# ESP32_USB_INTERFACE_NOESP.net
KiCad netlist of a schematic drawn in EAGLE
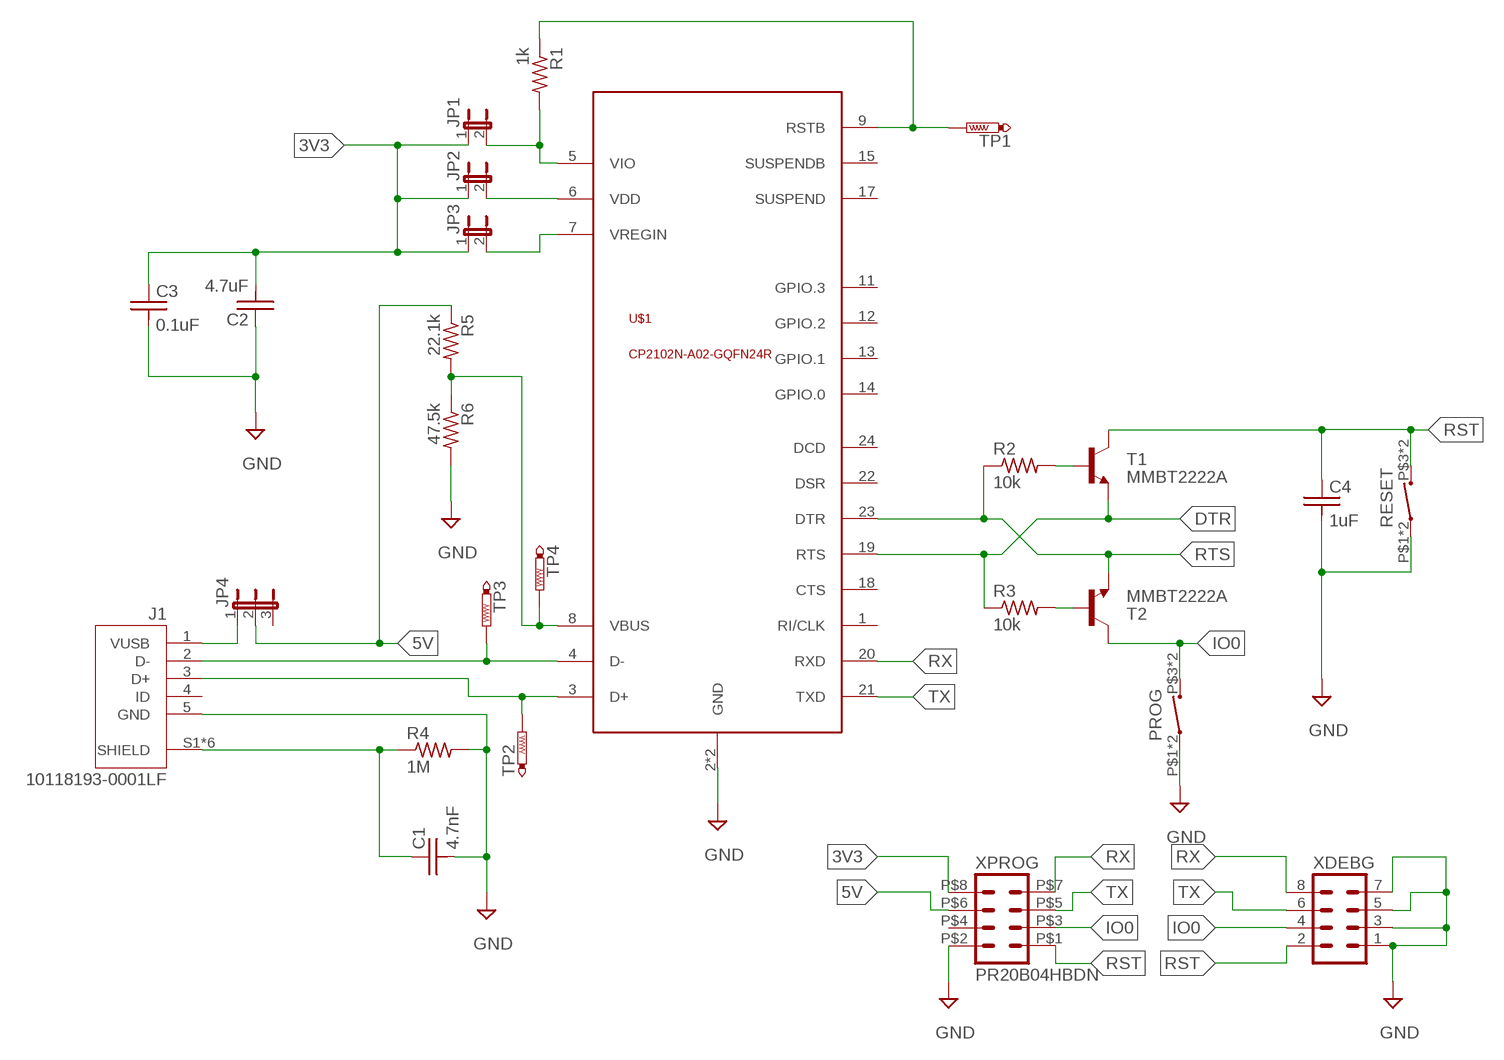
[diagram p0: schematic, sheet 1]

(export (version "E")
  (design (tool "Eeschema 10.0.6"))
  (components
    (comp (ref "C1")
      (value "4.7nF")
      (footprint "eagle-import:C0603")
      (libsource (lib "eagle-import") (part "C0603"))
    )
    (comp (ref "C2")
      (value "4.7uF")
      (footprint "eagle-import:C0603")
      (libsource (lib "eagle-import") (part "C0603"))
    )
    (comp (ref "C3")
      (value "0.1uF")
      (footprint "eagle-import:C0603")
      (libsource (lib "eagle-import") (part "C0603"))
    )
    (comp (ref "C4")
      (value "1uF")
      (footprint "eagle-import:C0603")
      (libsource (lib "eagle-import") (part "C0603"))
    )
    (comp (ref "J1")
      (value "10118193-0001LF")
      (footprint "eagle-import:FCI_10118193-0001LF")
      (fields (field (name "DIGI-KEY_PART_NUMBER") "609-4616-1-ND") (field (name "MF") "Amphenol ICC"))
      (libsource (lib "eagle-import") (part "10118193-0001LF"))
    )
    (comp (ref "JP1")
      (value "JP1E")
      (footprint "eagle-import:JP1")
      (libsource (lib "eagle-import") (part "JP1E"))
    )
    (comp (ref "JP2")
      (value "JP1E")
      (footprint "eagle-import:JP1")
      (libsource (lib "eagle-import") (part "JP1E"))
    )
    (comp (ref "JP3")
      (value "JP1E")
      (footprint "eagle-import:JP1")
      (libsource (lib "eagle-import") (part "JP1E"))
    )
    (comp (ref "JP4")
      (value "JP2E")
      (footprint "eagle-import:JP2")
      (libsource (lib "eagle-import") (part "JP2E"))
    )
    (comp (ref "PROG")
      (value "MOMENTARY_SWITCH")
      (footprint "eagle-import:PTS645")
      (libsource (lib "eagle-import") (part "MOMENTARY_SWITCH"))
    )
    (comp (ref "R1")
      (value "1k")
      (footprint "eagle-import:R0603")
      (libsource (lib "eagle-import") (part "R0603"))
    )
    (comp (ref "R2")
      (value "10k")
      (footprint "eagle-import:R0603")
      (libsource (lib "eagle-import") (part "R0603"))
    )
    (comp (ref "R3")
      (value "10k")
      (footprint "eagle-import:R0603")
      (libsource (lib "eagle-import") (part "R0603"))
    )
    (comp (ref "R4")
      (value "1M")
      (footprint "eagle-import:R0603")
      (libsource (lib "eagle-import") (part "R0603"))
    )
    (comp (ref "R5")
      (value "22.1k")
      (footprint "eagle-import:R0603")
      (libsource (lib "eagle-import") (part "R0603"))
    )
    (comp (ref "R6")
      (value "47.5k")
      (footprint "eagle-import:R0603")
      (libsource (lib "eagle-import") (part "R0603"))
    )
    (comp (ref "RESET")
      (value "MOMENTARY_SWITCH")
      (footprint "eagle-import:PTS645")
      (libsource (lib "eagle-import") (part "MOMENTARY_SWITCH"))
    )
    (comp (ref "T1")
      (value "MMBT2222A")
      (footprint "eagle-import:SOT23-BEC")
      (libsource (lib "eagle-import") (part "-NPN-SOT23-BECMMBT2222ALT1"))
    )
    (comp (ref "T2")
      (value "MMBT2222A")
      (footprint "eagle-import:SOT23-BEC")
      (libsource (lib "eagle-import") (part "-NPN-SOT23-BECMMBT2222ALT1"))
    )
    (comp (ref "TP1")
      (value "PTR1TP10R")
      (footprint "eagle-import:TP10R")
      (libsource (lib "eagle-import") (part "PTR1TP10R"))
    )
    (comp (ref "TP2")
      (value "PTR1TP10R")
      (footprint "eagle-import:TP10R")
      (libsource (lib "eagle-import") (part "PTR1TP10R"))
    )
    (comp (ref "TP3")
      (value "PTR1TP10R")
      (footprint "eagle-import:TP10R")
      (libsource (lib "eagle-import") (part "PTR1TP10R"))
    )
    (comp (ref "TP4")
      (value "PTR1TP10R")
      (footprint "eagle-import:TP10R")
      (libsource (lib "eagle-import") (part "PTR1TP10R"))
    )
    (comp (ref "U$1")
      (value "CP2102N-A02-GQFN24R")
      (footprint "eagle-import:QFN24-4X4")
      (libsource (lib "eagle-import") (part "CP2102N-A02-GQFN24R"))
    )
    (comp (ref "XDEBG")
      (value "MA04-2")
      (footprint "eagle-import:MA04-2")
      (libsource (lib "eagle-import") (part "MA04-2"))
    )
    (comp (ref "XPROG")
      (value "PR20B04HBDN")
      (footprint "eagle-import:PR20B04HBDN")
      (libsource (lib "eagle-import") (part "PR20B04HBDN"))
    )
  )
  (nets
    (net (code "1") (name "3V3") (class "Default")
      (node (ref "C2") (pin "2") (pinfunction "2_2") (pintype "passive"))
      (node (ref "C3") (pin "1") (pinfunction "1_1") (pintype "passive"))
      (node (ref "JP1") (pin "1") (pinfunction "1_1") (pintype "passive"))
      (node (ref "JP2") (pin "1") (pinfunction "1_1") (pintype "passive"))
      (node (ref "JP3") (pin "1") (pinfunction "1_1") (pintype "passive"))
      (node (ref "XPROG") (pin "P$8") (pinfunction "8_P$8") (pintype "passive"))
    )
    (net (code "2") (name "5V") (class "Default")
      (node (ref "JP4") (pin "2") (pinfunction "2_2") (pintype "passive"))
      (node (ref "R5") (pin "1") (pinfunction "1_1") (pintype "passive"))
      (node (ref "XPROG") (pin "P$6") (pinfunction "6_P$6") (pintype "passive"))
    )
    (net (code "3") (name "DTR") (class "Default")
      (node (ref "R3") (pin "1") (pinfunction "1_1") (pintype "passive"))
      (node (ref "T1") (pin "E") (pinfunction "E_E") (pintype "passive"))
      (node (ref "U$1") (pin "19") (pinfunction "RTS_19") (pintype "bidirectional"))
    )
    (net (code "4") (name "GND") (class "Default")
      (node (ref "C1") (pin "2") (pinfunction "2_2") (pintype "passive"))
      (node (ref "C2") (pin "1") (pinfunction "1_1") (pintype "passive"))
      (node (ref "C3") (pin "2") (pinfunction "2_2") (pintype "passive"))
      (node (ref "C4") (pin "2") (pinfunction "2_2") (pintype "passive"))
      (node (ref "J1") (pin "5") (pinfunction "GND_5") (pintype "passive"))
      (node (ref "PROG") (pin "P$1") (pinfunction "1_P$1") (pintype "passive"))
      (node (ref "PROG") (pin "P$2") (pinfunction "1_P$2") (pintype "passive"))
      (node (ref "R4") (pin "2") (pinfunction "2_2") (pintype "passive"))
      (node (ref "R6") (pin "2") (pinfunction "2_2") (pintype "passive"))
      (node (ref "RESET") (pin "P$1") (pinfunction "1_P$1") (pintype "passive"))
      (node (ref "RESET") (pin "P$2") (pinfunction "1_P$2") (pintype "passive"))
      (node (ref "U$1") (pin "2") (pinfunction "GND_2") (pintype "bidirectional"))
      (node (ref "U$1") (pin "EXP") (pinfunction "GND_EXP") (pintype "bidirectional"))
      (node (ref "XDEBG") (pin "1") (pinfunction "1_1") (pintype "passive"))
      (node (ref "XDEBG") (pin "3") (pinfunction "3_3") (pintype "passive"))
      (node (ref "XDEBG") (pin "5") (pinfunction "5_5") (pintype "passive"))
      (node (ref "XDEBG") (pin "7") (pinfunction "7_7") (pintype "passive"))
      (node (ref "XPROG") (pin "P$2") (pinfunction "2_P$2") (pintype "passive"))
    )
    (net (code "5") (name "IO0") (class "Default")
      (node (ref "PROG") (pin "P$3") (pinfunction "2_P$3") (pintype "passive"))
      (node (ref "PROG") (pin "P$4") (pinfunction "2_P$4") (pintype "passive"))
      (node (ref "T2") (pin "C") (pinfunction "C_C") (pintype "passive"))
      (node (ref "XDEBG") (pin "4") (pinfunction "4_4") (pintype "passive"))
      (node (ref "XPROG") (pin "P$3") (pinfunction "3_P$3") (pintype "passive"))
    )
    (net (code "6") (name "Net-(C1-Pad1)") (class "Default")
      (node (ref "C1") (pin "1") (pinfunction "1_1") (pintype "passive"))
      (node (ref "J1") (pin "S1") (pinfunction "SHIELD_S1") (pintype "passive"))
      (node (ref "J1") (pin "S2") (pinfunction "SHIELD_S2") (pintype "passive"))
      (node (ref "J1") (pin "S3") (pinfunction "SHIELD_S3") (pintype "passive"))
      (node (ref "J1") (pin "S4") (pinfunction "SHIELD_S4") (pintype "passive"))
      (node (ref "J1") (pin "S5") (pinfunction "SHIELD_S5") (pintype "passive"))
      (node (ref "J1") (pin "S6") (pinfunction "SHIELD_S6") (pintype "passive"))
      (node (ref "R4") (pin "1") (pinfunction "1_1") (pintype "passive"))
    )
    (net (code "7") (name "Net-(J1-D+)") (class "Default")
      (node (ref "J1") (pin "3") (pinfunction "D+_3") (pintype "passive"))
      (node (ref "TP2") (pin "TP") (pinfunction "TP_TP") (pintype "input"))
      (node (ref "U$1") (pin "3") (pinfunction "D+_3") (pintype "bidirectional"))
    )
    (net (code "8") (name "Net-(J1-D-)") (class "Default")
      (node (ref "J1") (pin "2") (pinfunction "D-_2") (pintype "passive"))
      (node (ref "TP3") (pin "TP") (pinfunction "TP_TP") (pintype "input"))
      (node (ref "U$1") (pin "4") (pinfunction "D-_4") (pintype "bidirectional"))
    )
    (net (code "9") (name "Net-(J1-VUSB)") (class "Default")
      (node (ref "J1") (pin "1") (pinfunction "VUSB_1") (pintype "passive"))
      (node (ref "JP4") (pin "1") (pinfunction "1_1") (pintype "passive"))
    )
    (net (code "10") (name "Net-(R2-Pad2)") (class "Default")
      (node (ref "R2") (pin "2") (pinfunction "2_2") (pintype "passive"))
      (node (ref "T1") (pin "B") (pinfunction "B_B") (pintype "passive"))
    )
    (net (code "11") (name "Net-(R3-Pad2)") (class "Default")
      (node (ref "R3") (pin "2") (pinfunction "2_2") (pintype "passive"))
      (node (ref "T2") (pin "B") (pinfunction "B_B") (pintype "passive"))
    )
    (net (code "12") (name "Net-(U$1-RSTB)") (class "Default")
      (node (ref "R1") (pin "1") (pinfunction "1_1") (pintype "passive"))
      (node (ref "TP1") (pin "TP") (pinfunction "TP_TP") (pintype "input"))
      (node (ref "U$1") (pin "9") (pinfunction "RSTB_9") (pintype "bidirectional"))
    )
    (net (code "13") (name "Net-(U$1-VBUS)") (class "Default")
      (node (ref "R5") (pin "2") (pinfunction "2_2") (pintype "passive"))
      (node (ref "R6") (pin "1") (pinfunction "1_1") (pintype "passive"))
      (node (ref "TP4") (pin "TP") (pinfunction "TP_TP") (pintype "input"))
      (node (ref "U$1") (pin "8") (pinfunction "VBUS_8") (pintype "bidirectional"))
    )
    (net (code "14") (name "Net-(U$1-VDD)") (class "Default")
      (node (ref "JP2") (pin "2") (pinfunction "2_2") (pintype "passive"))
      (node (ref "U$1") (pin "6") (pinfunction "VDD_6") (pintype "bidirectional"))
    )
    (net (code "15") (name "Net-(U$1-VIO)") (class "Default")
      (node (ref "JP1") (pin "2") (pinfunction "2_2") (pintype "passive"))
      (node (ref "R1") (pin "2") (pinfunction "2_2") (pintype "passive"))
      (node (ref "U$1") (pin "5") (pinfunction "VIO_5") (pintype "bidirectional"))
    )
    (net (code "16") (name "Net-(U$1-VREGIN)") (class "Default")
      (node (ref "JP3") (pin "2") (pinfunction "2_2") (pintype "passive"))
      (node (ref "U$1") (pin "7") (pinfunction "VREGIN_7") (pintype "bidirectional"))
    )
    (net (code "17") (name "RST") (class "Default")
      (node (ref "C4") (pin "1") (pinfunction "1_1") (pintype "passive"))
      (node (ref "RESET") (pin "P$3") (pinfunction "2_P$3") (pintype "passive"))
      (node (ref "RESET") (pin "P$4") (pinfunction "2_P$4") (pintype "passive"))
      (node (ref "T1") (pin "C") (pinfunction "C_C") (pintype "passive"))
      (node (ref "XDEBG") (pin "2") (pinfunction "2_2") (pintype "passive"))
      (node (ref "XPROG") (pin "P$1") (pinfunction "1_P$1") (pintype "passive"))
    )
    (net (code "18") (name "RTS") (class "Default")
      (node (ref "R2") (pin "1") (pinfunction "1_1") (pintype "passive"))
      (node (ref "T2") (pin "E") (pinfunction "E_E") (pintype "passive"))
      (node (ref "U$1") (pin "23") (pinfunction "DTR_23") (pintype "bidirectional"))
    )
    (net (code "19") (name "RX") (class "Default")
      (node (ref "U$1") (pin "20") (pinfunction "RXD_20") (pintype "bidirectional"))
      (node (ref "XDEBG") (pin "8") (pinfunction "8_8") (pintype "passive"))
      (node (ref "XPROG") (pin "P$7") (pinfunction "7_P$7") (pintype "passive"))
    )
    (net (code "20") (name "TX") (class "Default")
      (node (ref "U$1") (pin "21") (pinfunction "TXD_21") (pintype "bidirectional"))
      (node (ref "XDEBG") (pin "6") (pinfunction "6_6") (pintype "passive"))
      (node (ref "XPROG") (pin "P$5") (pinfunction "5_P$5") (pintype "passive"))
    )
    (net (code "21") (name "unconnected-(J1-ID-Pad4)") (class "Default")
      (node (ref "J1") (pin "4") (pinfunction "ID_4") (pintype "passive"))
    )
    (net (code "22") (name "unconnected-(JP4-Pad3)") (class "Default")
      (node (ref "JP4") (pin "3") (pinfunction "3_3") (pintype "passive"))
    )
    (net (code "23") (name "unconnected-(U$1-CTS-Pad18)") (class "Default")
      (node (ref "U$1") (pin "18") (pinfunction "CTS_18") (pintype "bidirectional"))
    )
    (net (code "24") (name "unconnected-(U$1-DCD-Pad24)") (class "Default")
      (node (ref "U$1") (pin "24") (pinfunction "DCD_24") (pintype "bidirectional"))
    )
    (net (code "25") (name "unconnected-(U$1-DSR-Pad22)") (class "Default")
      (node (ref "U$1") (pin "22") (pinfunction "DSR_22") (pintype "bidirectional"))
    )
    (net (code "26") (name "unconnected-(U$1-GPIO.0-Pad14)") (class "Default")
      (node (ref "U$1") (pin "14") (pinfunction "GPIO.0_14") (pintype "bidirectional"))
    )
    (net (code "27") (name "unconnected-(U$1-GPIO.1-Pad13)") (class "Default")
      (node (ref "U$1") (pin "13") (pinfunction "GPIO.1_13") (pintype "bidirectional"))
    )
    (net (code "28") (name "unconnected-(U$1-GPIO.2-Pad12)") (class "Default")
      (node (ref "U$1") (pin "12") (pinfunction "GPIO.2_12") (pintype "bidirectional"))
    )
    (net (code "29") (name "unconnected-(U$1-GPIO.3-Pad11)") (class "Default")
      (node (ref "U$1") (pin "11") (pinfunction "GPIO.3_11") (pintype "bidirectional"))
    )
    (net (code "30") (name "unconnected-(U$1-RI{slash}CLK-Pad1)") (class "Default")
      (node (ref "U$1") (pin "1") (pinfunction "RI/CLK_1") (pintype "bidirectional"))
    )
    (net (code "31") (name "unconnected-(U$1-SUSPEND-Pad17)") (class "Default")
      (node (ref "U$1") (pin "17") (pinfunction "SUSPEND_17") (pintype "bidirectional"))
    )
    (net (code "32") (name "unconnected-(U$1-SUSPENDB-Pad15)") (class "Default")
      (node (ref "U$1") (pin "15") (pinfunction "SUSPENDB_15") (pintype "bidirectional"))
    )
    (net (code "33") (name "unconnected-(XPROG-4-PadP$4)") (class "Default")
      (node (ref "XPROG") (pin "P$4") (pinfunction "4_P$4") (pintype "passive"))
    )
  )
)
